# osh-2l-cpwg.net
KiCad netlist of a schematic drawn in EAGLE
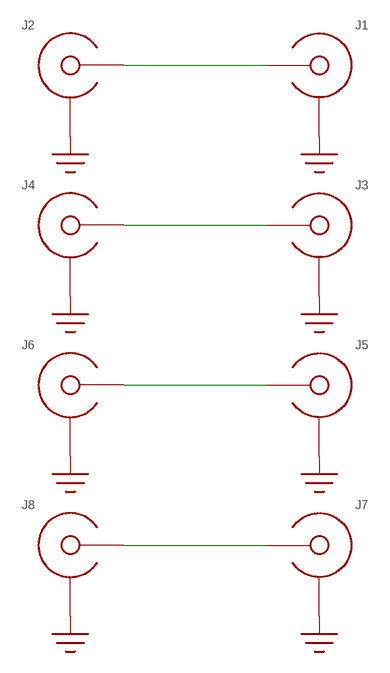
[diagram p0: schematic, sheet 1]

(export (version "E")
  (design (tool "Eeschema 10.0.6"))
  (components
    (comp (ref "J1")
      (value "SMA-EDGE-LAUNCH4020_TAPER")
      (footprint "eagle-import:SMA_EDGE_LAUNCH_2L_4020_TAPER")
      (libsource (lib "eagle-import") (part "SMA-EDGE-LAUNCH4020_TAPER"))
    )
    (comp (ref "J2")
      (value "SMA-EDGE-LAUNCHCUT-PIN")
      (footprint "eagle-import:SMA_EDGE_LAUNCH_2L_4020_CUT_PIN")
      (libsource (lib "eagle-import") (part "SMA-EDGE-LAUNCHCUT-PIN"))
    )
    (comp (ref "J3")
      (value "SMA-EDGE-LAUNCH4020_TAPER")
      (footprint "eagle-import:SMA_EDGE_LAUNCH_2L_4020_TAPER")
      (libsource (lib "eagle-import") (part "SMA-EDGE-LAUNCH4020_TAPER"))
    )
    (comp (ref "J4")
      (value "SMA-EDGE-LAUNCHCUT-PIN")
      (footprint "eagle-import:SMA_EDGE_LAUNCH_2L_4020_CUT_PIN")
      (libsource (lib "eagle-import") (part "SMA-EDGE-LAUNCHCUT-PIN"))
    )
    (comp (ref "J5")
      (value "SMA-EDGE-LAUNCH4020_TAPER")
      (footprint "eagle-import:SMA_EDGE_LAUNCH_2L_4020_TAPER")
      (libsource (lib "eagle-import") (part "SMA-EDGE-LAUNCH4020_TAPER"))
    )
    (comp (ref "J6")
      (value "SMA-EDGE-LAUNCHCUT-PIN")
      (footprint "eagle-import:SMA_EDGE_LAUNCH_2L_4020_CUT_PIN")
      (libsource (lib "eagle-import") (part "SMA-EDGE-LAUNCHCUT-PIN"))
    )
    (comp (ref "J7")
      (value "SMA-EDGE-LAUNCH4020_TAPER")
      (footprint "eagle-import:SMA_EDGE_LAUNCH_2L_4020_TAPER")
      (libsource (lib "eagle-import") (part "SMA-EDGE-LAUNCH4020_TAPER"))
    )
    (comp (ref "J8")
      (value "SMA-EDGE-LAUNCHCUT-PIN")
      (footprint "eagle-import:SMA_EDGE_LAUNCH_2L_4020_CUT_PIN")
      (libsource (lib "eagle-import") (part "SMA-EDGE-LAUNCHCUT-PIN"))
    )
  )
  (nets
    (net (code "1") (name "GND") (class "Default")
      (node (ref "J1") (pin "BOTTOM_GND") (pinfunction "SHIELD_BOTTOM_GND") (pintype "bidirectional"))
      (node (ref "J1") (pin "GND@1") (pinfunction "SHIELD_GND@1") (pintype "bidirectional"))
      (node (ref "J1") (pin "GND@14") (pinfunction "SHIELD_GND@14") (pintype "bidirectional"))
      (node (ref "J1") (pin "GND@15") (pinfunction "SHIELD_GND@15") (pintype "bidirectional"))
      (node (ref "J1") (pin "GND@16") (pinfunction "SHIELD_GND@16") (pintype "bidirectional"))
      (node (ref "J1") (pin "GND@17") (pinfunction "SHIELD_GND@17") (pintype "bidirectional"))
      (node (ref "J1") (pin "GND@2") (pinfunction "SHIELD_GND@2") (pintype "bidirectional"))
      (node (ref "J1") (pin "GND@3") (pinfunction "SHIELD_GND@3") (pintype "bidirectional"))
      (node (ref "J1") (pin "GND@4") (pinfunction "SHIELD_GND@4") (pintype "bidirectional"))
      (node (ref "J1") (pin "GND@5") (pinfunction "SHIELD_GND@5") (pintype "bidirectional"))
      (node (ref "J1") (pin "GND@6") (pinfunction "SHIELD_GND@6") (pintype "bidirectional"))
      (node (ref "J1") (pin "GND@7") (pinfunction "SHIELD_GND@7") (pintype "bidirectional"))
      (node (ref "J1") (pin "GND@8") (pinfunction "SHIELD_GND@8") (pintype "bidirectional"))
      (node (ref "J1") (pin "GND_PAD1") (pinfunction "SHIELD_GND_PAD1") (pintype "bidirectional"))
      (node (ref "J1") (pin "GND_PAD2") (pinfunction "SHIELD_GND_PAD2") (pintype "bidirectional"))
      (node (ref "J1") (pin "P$1") (pinfunction "SHIELD_P$1") (pintype "bidirectional"))
      (node (ref "J1") (pin "P$2") (pinfunction "SHIELD_P$2") (pintype "bidirectional"))
      (node (ref "J2") (pin "BOTTOM_GND") (pinfunction "SHIELD_BOTTOM_GND") (pintype "bidirectional"))
      (node (ref "J2") (pin "GND@1") (pinfunction "SHIELD_GND@1") (pintype "bidirectional"))
      (node (ref "J2") (pin "GND@14") (pinfunction "SHIELD_GND@14") (pintype "bidirectional"))
      (node (ref "J2") (pin "GND@15") (pinfunction "SHIELD_GND@15") (pintype "bidirectional"))
      (node (ref "J2") (pin "GND@16") (pinfunction "SHIELD_GND@16") (pintype "bidirectional"))
      (node (ref "J2") (pin "GND@17") (pinfunction "SHIELD_GND@17") (pintype "bidirectional"))
      (node (ref "J2") (pin "GND@2") (pinfunction "SHIELD_GND@2") (pintype "bidirectional"))
      (node (ref "J2") (pin "GND@3") (pinfunction "SHIELD_GND@3") (pintype "bidirectional"))
      (node (ref "J2") (pin "GND@4") (pinfunction "SHIELD_GND@4") (pintype "bidirectional"))
      (node (ref "J2") (pin "GND@5") (pinfunction "SHIELD_GND@5") (pintype "bidirectional"))
      (node (ref "J2") (pin "GND@6") (pinfunction "SHIELD_GND@6") (pintype "bidirectional"))
      (node (ref "J2") (pin "GND@7") (pinfunction "SHIELD_GND@7") (pintype "bidirectional"))
      (node (ref "J2") (pin "GND@8") (pinfunction "SHIELD_GND@8") (pintype "bidirectional"))
      (node (ref "J2") (pin "GND_PAD1") (pinfunction "SHIELD_GND_PAD1") (pintype "bidirectional"))
      (node (ref "J2") (pin "GND_PAD2") (pinfunction "SHIELD_GND_PAD2") (pintype "bidirectional"))
      (node (ref "J3") (pin "BOTTOM_GND") (pinfunction "SHIELD_BOTTOM_GND") (pintype "bidirectional"))
      (node (ref "J3") (pin "GND@1") (pinfunction "SHIELD_GND@1") (pintype "bidirectional"))
      (node (ref "J3") (pin "GND@14") (pinfunction "SHIELD_GND@14") (pintype "bidirectional"))
      (node (ref "J3") (pin "GND@15") (pinfunction "SHIELD_GND@15") (pintype "bidirectional"))
      (node (ref "J3") (pin "GND@16") (pinfunction "SHIELD_GND@16") (pintype "bidirectional"))
      (node (ref "J3") (pin "GND@17") (pinfunction "SHIELD_GND@17") (pintype "bidirectional"))
      (node (ref "J3") (pin "GND@2") (pinfunction "SHIELD_GND@2") (pintype "bidirectional"))
      (node (ref "J3") (pin "GND@3") (pinfunction "SHIELD_GND@3") (pintype "bidirectional"))
      (node (ref "J3") (pin "GND@4") (pinfunction "SHIELD_GND@4") (pintype "bidirectional"))
      (node (ref "J3") (pin "GND@5") (pinfunction "SHIELD_GND@5") (pintype "bidirectional"))
      (node (ref "J3") (pin "GND@6") (pinfunction "SHIELD_GND@6") (pintype "bidirectional"))
      (node (ref "J3") (pin "GND@7") (pinfunction "SHIELD_GND@7") (pintype "bidirectional"))
      (node (ref "J3") (pin "GND@8") (pinfunction "SHIELD_GND@8") (pintype "bidirectional"))
      (node (ref "J3") (pin "GND_PAD1") (pinfunction "SHIELD_GND_PAD1") (pintype "bidirectional"))
      (node (ref "J3") (pin "GND_PAD2") (pinfunction "SHIELD_GND_PAD2") (pintype "bidirectional"))
      (node (ref "J3") (pin "P$1") (pinfunction "SHIELD_P$1") (pintype "bidirectional"))
      (node (ref "J3") (pin "P$2") (pinfunction "SHIELD_P$2") (pintype "bidirectional"))
      (node (ref "J4") (pin "BOTTOM_GND") (pinfunction "SHIELD_BOTTOM_GND") (pintype "bidirectional"))
      (node (ref "J4") (pin "GND@1") (pinfunction "SHIELD_GND@1") (pintype "bidirectional"))
      (node (ref "J4") (pin "GND@14") (pinfunction "SHIELD_GND@14") (pintype "bidirectional"))
      (node (ref "J4") (pin "GND@15") (pinfunction "SHIELD_GND@15") (pintype "bidirectional"))
      (node (ref "J4") (pin "GND@16") (pinfunction "SHIELD_GND@16") (pintype "bidirectional"))
      (node (ref "J4") (pin "GND@17") (pinfunction "SHIELD_GND@17") (pintype "bidirectional"))
      (node (ref "J4") (pin "GND@2") (pinfunction "SHIELD_GND@2") (pintype "bidirectional"))
      (node (ref "J4") (pin "GND@3") (pinfunction "SHIELD_GND@3") (pintype "bidirectional"))
      (node (ref "J4") (pin "GND@4") (pinfunction "SHIELD_GND@4") (pintype "bidirectional"))
      (node (ref "J4") (pin "GND@5") (pinfunction "SHIELD_GND@5") (pintype "bidirectional"))
      (node (ref "J4") (pin "GND@6") (pinfunction "SHIELD_GND@6") (pintype "bidirectional"))
      (node (ref "J4") (pin "GND@7") (pinfunction "SHIELD_GND@7") (pintype "bidirectional"))
      (node (ref "J4") (pin "GND@8") (pinfunction "SHIELD_GND@8") (pintype "bidirectional"))
      (node (ref "J4") (pin "GND_PAD1") (pinfunction "SHIELD_GND_PAD1") (pintype "bidirectional"))
      (node (ref "J4") (pin "GND_PAD2") (pinfunction "SHIELD_GND_PAD2") (pintype "bidirectional"))
      (node (ref "J5") (pin "BOTTOM_GND") (pinfunction "SHIELD_BOTTOM_GND") (pintype "bidirectional"))
      (node (ref "J5") (pin "GND@1") (pinfunction "SHIELD_GND@1") (pintype "bidirectional"))
      (node (ref "J5") (pin "GND@14") (pinfunction "SHIELD_GND@14") (pintype "bidirectional"))
      (node (ref "J5") (pin "GND@15") (pinfunction "SHIELD_GND@15") (pintype "bidirectional"))
      (node (ref "J5") (pin "GND@16") (pinfunction "SHIELD_GND@16") (pintype "bidirectional"))
      (node (ref "J5") (pin "GND@17") (pinfunction "SHIELD_GND@17") (pintype "bidirectional"))
      (node (ref "J5") (pin "GND@2") (pinfunction "SHIELD_GND@2") (pintype "bidirectional"))
      (node (ref "J5") (pin "GND@3") (pinfunction "SHIELD_GND@3") (pintype "bidirectional"))
      (node (ref "J5") (pin "GND@4") (pinfunction "SHIELD_GND@4") (pintype "bidirectional"))
      (node (ref "J5") (pin "GND@5") (pinfunction "SHIELD_GND@5") (pintype "bidirectional"))
      (node (ref "J5") (pin "GND@6") (pinfunction "SHIELD_GND@6") (pintype "bidirectional"))
      (node (ref "J5") (pin "GND@7") (pinfunction "SHIELD_GND@7") (pintype "bidirectional"))
      (node (ref "J5") (pin "GND@8") (pinfunction "SHIELD_GND@8") (pintype "bidirectional"))
      (node (ref "J5") (pin "GND_PAD1") (pinfunction "SHIELD_GND_PAD1") (pintype "bidirectional"))
      (node (ref "J5") (pin "GND_PAD2") (pinfunction "SHIELD_GND_PAD2") (pintype "bidirectional"))
      (node (ref "J5") (pin "P$1") (pinfunction "SHIELD_P$1") (pintype "bidirectional"))
      (node (ref "J5") (pin "P$2") (pinfunction "SHIELD_P$2") (pintype "bidirectional"))
      (node (ref "J6") (pin "BOTTOM_GND") (pinfunction "SHIELD_BOTTOM_GND") (pintype "bidirectional"))
      (node (ref "J6") (pin "GND@1") (pinfunction "SHIELD_GND@1") (pintype "bidirectional"))
      (node (ref "J6") (pin "GND@14") (pinfunction "SHIELD_GND@14") (pintype "bidirectional"))
      (node (ref "J6") (pin "GND@15") (pinfunction "SHIELD_GND@15") (pintype "bidirectional"))
      (node (ref "J6") (pin "GND@16") (pinfunction "SHIELD_GND@16") (pintype "bidirectional"))
      (node (ref "J6") (pin "GND@17") (pinfunction "SHIELD_GND@17") (pintype "bidirectional"))
      (node (ref "J6") (pin "GND@2") (pinfunction "SHIELD_GND@2") (pintype "bidirectional"))
      (node (ref "J6") (pin "GND@3") (pinfunction "SHIELD_GND@3") (pintype "bidirectional"))
      (node (ref "J6") (pin "GND@4") (pinfunction "SHIELD_GND@4") (pintype "bidirectional"))
      (node (ref "J6") (pin "GND@5") (pinfunction "SHIELD_GND@5") (pintype "bidirectional"))
      (node (ref "J6") (pin "GND@6") (pinfunction "SHIELD_GND@6") (pintype "bidirectional"))
      (node (ref "J6") (pin "GND@7") (pinfunction "SHIELD_GND@7") (pintype "bidirectional"))
      (node (ref "J6") (pin "GND@8") (pinfunction "SHIELD_GND@8") (pintype "bidirectional"))
      (node (ref "J6") (pin "GND_PAD1") (pinfunction "SHIELD_GND_PAD1") (pintype "bidirectional"))
      (node (ref "J6") (pin "GND_PAD2") (pinfunction "SHIELD_GND_PAD2") (pintype "bidirectional"))
      (node (ref "J7") (pin "BOTTOM_GND") (pinfunction "SHIELD_BOTTOM_GND") (pintype "bidirectional"))
      (node (ref "J7") (pin "GND@1") (pinfunction "SHIELD_GND@1") (pintype "bidirectional"))
      (node (ref "J7") (pin "GND@14") (pinfunction "SHIELD_GND@14") (pintype "bidirectional"))
      (node (ref "J7") (pin "GND@15") (pinfunction "SHIELD_GND@15") (pintype "bidirectional"))
      (node (ref "J7") (pin "GND@16") (pinfunction "SHIELD_GND@16") (pintype "bidirectional"))
      (node (ref "J7") (pin "GND@17") (pinfunction "SHIELD_GND@17") (pintype "bidirectional"))
      (node (ref "J7") (pin "GND@2") (pinfunction "SHIELD_GND@2") (pintype "bidirectional"))
      (node (ref "J7") (pin "GND@3") (pinfunction "SHIELD_GND@3") (pintype "bidirectional"))
      (node (ref "J7") (pin "GND@4") (pinfunction "SHIELD_GND@4") (pintype "bidirectional"))
      (node (ref "J7") (pin "GND@5") (pinfunction "SHIELD_GND@5") (pintype "bidirectional"))
      (node (ref "J7") (pin "GND@6") (pinfunction "SHIELD_GND@6") (pintype "bidirectional"))
      (node (ref "J7") (pin "GND@7") (pinfunction "SHIELD_GND@7") (pintype "bidirectional"))
      (node (ref "J7") (pin "GND@8") (pinfunction "SHIELD_GND@8") (pintype "bidirectional"))
      (node (ref "J7") (pin "GND_PAD1") (pinfunction "SHIELD_GND_PAD1") (pintype "bidirectional"))
      (node (ref "J7") (pin "GND_PAD2") (pinfunction "SHIELD_GND_PAD2") (pintype "bidirectional"))
      (node (ref "J7") (pin "P$1") (pinfunction "SHIELD_P$1") (pintype "bidirectional"))
      (node (ref "J7") (pin "P$2") (pinfunction "SHIELD_P$2") (pintype "bidirectional"))
      (node (ref "J8") (pin "BOTTOM_GND") (pinfunction "SHIELD_BOTTOM_GND") (pintype "bidirectional"))
      (node (ref "J8") (pin "GND@1") (pinfunction "SHIELD_GND@1") (pintype "bidirectional"))
      (node (ref "J8") (pin "GND@14") (pinfunction "SHIELD_GND@14") (pintype "bidirectional"))
      (node (ref "J8") (pin "GND@15") (pinfunction "SHIELD_GND@15") (pintype "bidirectional"))
      (node (ref "J8") (pin "GND@16") (pinfunction "SHIELD_GND@16") (pintype "bidirectional"))
      (node (ref "J8") (pin "GND@17") (pinfunction "SHIELD_GND@17") (pintype "bidirectional"))
      (node (ref "J8") (pin "GND@2") (pinfunction "SHIELD_GND@2") (pintype "bidirectional"))
      (node (ref "J8") (pin "GND@3") (pinfunction "SHIELD_GND@3") (pintype "bidirectional"))
      (node (ref "J8") (pin "GND@4") (pinfunction "SHIELD_GND@4") (pintype "bidirectional"))
      (node (ref "J8") (pin "GND@5") (pinfunction "SHIELD_GND@5") (pintype "bidirectional"))
      (node (ref "J8") (pin "GND@6") (pinfunction "SHIELD_GND@6") (pintype "bidirectional"))
      (node (ref "J8") (pin "GND@7") (pinfunction "SHIELD_GND@7") (pintype "bidirectional"))
      (node (ref "J8") (pin "GND@8") (pinfunction "SHIELD_GND@8") (pintype "bidirectional"))
      (node (ref "J8") (pin "GND_PAD1") (pinfunction "SHIELD_GND_PAD1") (pintype "bidirectional"))
      (node (ref "J8") (pin "GND_PAD2") (pinfunction "SHIELD_GND_PAD2") (pintype "bidirectional"))
    )
    (net (code "2") (name "Net-(J1-CENTER)") (class "Default")
      (node (ref "J1") (pin "CENTER@1") (pinfunction "CENTER_CENTER@1") (pintype "bidirectional"))
      (node (ref "J2") (pin "CENTER@1") (pinfunction "CENTER_CENTER@1") (pintype "bidirectional"))
      (node (ref "J2") (pin "CENTER@3") (pinfunction "CENTER_CENTER@3") (pintype "bidirectional"))
    )
    (net (code "3") (name "Net-(J3-CENTER)") (class "Default")
      (node (ref "J3") (pin "CENTER@1") (pinfunction "CENTER_CENTER@1") (pintype "bidirectional"))
      (node (ref "J4") (pin "CENTER@1") (pinfunction "CENTER_CENTER@1") (pintype "bidirectional"))
      (node (ref "J4") (pin "CENTER@3") (pinfunction "CENTER_CENTER@3") (pintype "bidirectional"))
    )
    (net (code "4") (name "Net-(J5-CENTER)") (class "Default")
      (node (ref "J5") (pin "CENTER@1") (pinfunction "CENTER_CENTER@1") (pintype "bidirectional"))
      (node (ref "J6") (pin "CENTER@1") (pinfunction "CENTER_CENTER@1") (pintype "bidirectional"))
      (node (ref "J6") (pin "CENTER@3") (pinfunction "CENTER_CENTER@3") (pintype "bidirectional"))
    )
    (net (code "5") (name "Net-(J7-CENTER)") (class "Default")
      (node (ref "J7") (pin "CENTER@1") (pinfunction "CENTER_CENTER@1") (pintype "bidirectional"))
      (node (ref "J8") (pin "CENTER@1") (pinfunction "CENTER_CENTER@1") (pintype "bidirectional"))
      (node (ref "J8") (pin "CENTER@3") (pinfunction "CENTER_CENTER@3") (pintype "bidirectional"))
    )
  )
)
